# lampu_tidur.net
KiCad netlist of a schematic drawn in EAGLE
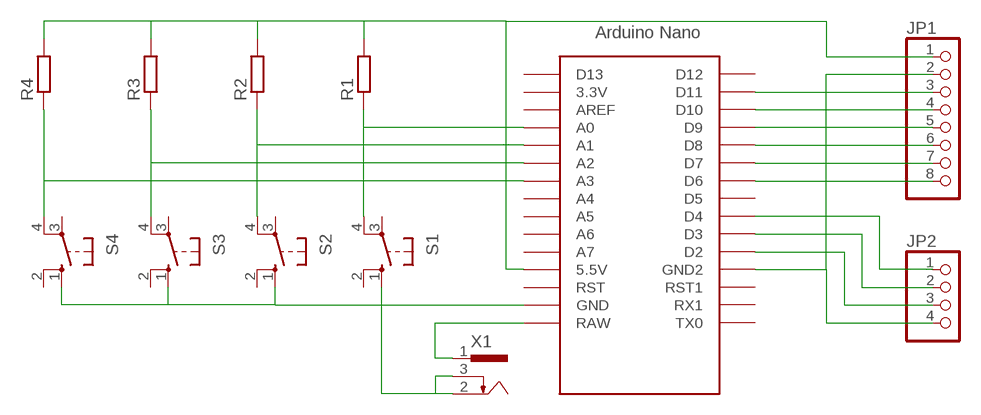
[diagram p0: schematic, sheet 1]

(export (version "E")
  (design (tool "Eeschema 10.0.6"))
  (components
    (comp (ref "JP1")
      (value "PINHD-1X8")
      (footprint "eagle-import:1X08")
      (libsource (lib "eagle-import") (part "PINHD-1X8"))
    )
    (comp (ref "JP2")
      (value "PINHD-1X4")
      (footprint "eagle-import:1X04")
      (libsource (lib "eagle-import") (part "PINHD-1X4"))
    )
    (comp (ref "R1")
      (value "R-EU_0204/7")
      (footprint "eagle-import:0204_7")
      (libsource (lib "eagle-import") (part "R-EU_0204/7"))
    )
    (comp (ref "R2")
      (value "R-EU_0204/7")
      (footprint "eagle-import:0204_7")
      (libsource (lib "eagle-import") (part "R-EU_0204/7"))
    )
    (comp (ref "R3")
      (value "R-EU_0204/7")
      (footprint "eagle-import:0204_7")
      (libsource (lib "eagle-import") (part "R-EU_0204/7"))
    )
    (comp (ref "R4")
      (value "R-EU_0204/7")
      (footprint "eagle-import:0204_7")
      (libsource (lib "eagle-import") (part "R-EU_0204/7"))
    )
    (comp (ref "S1")
      (value "10-XX")
      (footprint "eagle-import:B3F-10XX")
      (fields (field (name "MPN") "B3F-1000"))
      (libsource (lib "eagle-import") (part "10-XX"))
    )
    (comp (ref "S2")
      (value "10-XX")
      (footprint "eagle-import:B3F-10XX")
      (fields (field (name "MPN") "B3F-1000"))
      (libsource (lib "eagle-import") (part "10-XX"))
    )
    (comp (ref "S3")
      (value "10-XX")
      (footprint "eagle-import:B3F-10XX")
      (fields (field (name "MPN") "B3F-1000"))
      (libsource (lib "eagle-import") (part "10-XX"))
    )
    (comp (ref "S4")
      (value "10-XX")
      (footprint "eagle-import:B3F-10XX")
      (fields (field (name "MPN") "B3F-1000"))
      (libsource (lib "eagle-import") (part "10-XX"))
    )
    (comp (ref "U$1")
      (value "NANO")
      (footprint "eagle-import:NANO")
      (libsource (lib "eagle-import") (part "NANO"))
    )
    (comp (ref "X1")
      (value "733980-62")
      (footprint "eagle-import:733980-62")
      (libsource (lib "eagle-import") (part "73398?0-62"))
    )
  )
  (nets
    (net (code "1") (name "Net-(JP1-Pad3)") (class "Default")
      (node (ref "JP1") (pin "3") (pinfunction "3_3") (pintype "passive"))
      (node (ref "U$1") (pin "D11") (pinfunction "D11_D11") (pintype "bidirectional"))
    )
    (net (code "2") (name "Net-(JP1-Pad4)") (class "Default")
      (node (ref "JP1") (pin "4") (pinfunction "4_4") (pintype "passive"))
      (node (ref "U$1") (pin "D10") (pinfunction "D10_D10") (pintype "bidirectional"))
    )
    (net (code "3") (name "Net-(JP1-Pad5)") (class "Default")
      (node (ref "JP1") (pin "5") (pinfunction "5_5") (pintype "passive"))
      (node (ref "U$1") (pin "D9") (pinfunction "D9_D9") (pintype "bidirectional"))
    )
    (net (code "4") (name "Net-(JP1-Pad6)") (class "Default")
      (node (ref "JP1") (pin "6") (pinfunction "6_6") (pintype "passive"))
      (node (ref "U$1") (pin "D8") (pinfunction "D8_D8") (pintype "bidirectional"))
    )
    (net (code "5") (name "Net-(JP1-Pad7)") (class "Default")
      (node (ref "JP1") (pin "7") (pinfunction "7_7") (pintype "passive"))
      (node (ref "U$1") (pin "D7") (pinfunction "D7_D7") (pintype "bidirectional"))
    )
    (net (code "6") (name "Net-(JP1-Pad8)") (class "Default")
      (node (ref "JP1") (pin "8") (pinfunction "8_8") (pintype "passive"))
      (node (ref "U$1") (pin "D6") (pinfunction "D6_D6") (pintype "bidirectional"))
    )
    (net (code "7") (name "Net-(JP2-Pad1)") (class "Default")
      (node (ref "JP2") (pin "1") (pinfunction "1_1") (pintype "passive"))
      (node (ref "U$1") (pin "D4") (pinfunction "D4_D4") (pintype "bidirectional"))
    )
    (net (code "8") (name "Net-(JP2-Pad2)") (class "Default")
      (node (ref "JP2") (pin "2") (pinfunction "2_2") (pintype "passive"))
      (node (ref "U$1") (pin "D3") (pinfunction "D3_D3") (pintype "bidirectional"))
    )
    (net (code "9") (name "Net-(JP2-Pad3)") (class "Default")
      (node (ref "JP2") (pin "3") (pinfunction "3_3") (pintype "passive"))
      (node (ref "U$1") (pin "D2") (pinfunction "D2_D2") (pintype "bidirectional"))
    )
    (net (code "10") (name "Net-(S1-P1)") (class "Default")
      (node (ref "R1") (pin "1") (pinfunction "1_1") (pintype "passive"))
      (node (ref "S1") (pin "4") (pinfunction "P1_4") (pintype "passive"))
      (node (ref "U$1") (pin "A0") (pinfunction "A0_A0") (pintype "bidirectional"))
    )
    (net (code "11") (name "Net-(S1-S)") (class "Default")
      (node (ref "S1") (pin "1") (pinfunction "S_1") (pintype "passive"))
      (node (ref "S2") (pin "1") (pinfunction "S_1") (pintype "passive"))
      (node (ref "S3") (pin "1") (pinfunction "S_1") (pintype "passive"))
      (node (ref "S4") (pin "1") (pinfunction "S_1") (pintype "passive"))
      (node (ref "U$1") (pin "GND") (pinfunction "GND_GND") (pintype "bidirectional"))
      (node (ref "X1") (pin "2") (pinfunction "2_2") (pintype "passive"))
      (node (ref "X1") (pin "3") (pinfunction "3_3") (pintype "passive"))
    )
    (net (code "12") (name "Net-(S2-P1)") (class "Default")
      (node (ref "R2") (pin "1") (pinfunction "1_1") (pintype "passive"))
      (node (ref "S2") (pin "4") (pinfunction "P1_4") (pintype "passive"))
      (node (ref "U$1") (pin "A1") (pinfunction "A1_A1") (pintype "bidirectional"))
    )
    (net (code "13") (name "Net-(S3-P1)") (class "Default")
      (node (ref "R3") (pin "1") (pinfunction "1_1") (pintype "passive"))
      (node (ref "S3") (pin "4") (pinfunction "P1_4") (pintype "passive"))
      (node (ref "U$1") (pin "A2") (pinfunction "A2_A2") (pintype "bidirectional"))
    )
    (net (code "14") (name "Net-(S4-P1)") (class "Default")
      (node (ref "R4") (pin "1") (pinfunction "1_1") (pintype "passive"))
      (node (ref "S4") (pin "4") (pinfunction "P1_4") (pintype "passive"))
      (node (ref "U$1") (pin "A3") (pinfunction "A3_A3") (pintype "bidirectional"))
    )
    (net (code "15") (name "Net-(U$1-5.5V)") (class "Default")
      (node (ref "JP1") (pin "1") (pinfunction "1_1") (pintype "passive"))
      (node (ref "R1") (pin "2") (pinfunction "2_2") (pintype "passive"))
      (node (ref "R2") (pin "2") (pinfunction "2_2") (pintype "passive"))
      (node (ref "R3") (pin "2") (pinfunction "2_2") (pintype "passive"))
      (node (ref "R4") (pin "2") (pinfunction "2_2") (pintype "passive"))
      (node (ref "U$1") (pin "5V") (pinfunction "5.5V_5V") (pintype "bidirectional"))
    )
    (net (code "16") (name "Net-(U$1-GND2)") (class "Default")
      (node (ref "JP1") (pin "2") (pinfunction "2_2") (pintype "passive"))
      (node (ref "JP2") (pin "4") (pinfunction "4_4") (pintype "passive"))
      (node (ref "U$1") (pin "GND1") (pinfunction "GND2_GND1") (pintype "bidirectional"))
    )
    (net (code "17") (name "Net-(U$1-PadRAW)") (class "Default")
      (node (ref "U$1") (pin "RAW") (pinfunction "RAW_RAW") (pintype "bidirectional"))
      (node (ref "X1") (pin "1") (pinfunction "1_1") (pintype "passive"))
    )
    (net (code "18") (name "unconnected-(S1-P-Pad3)") (class "Default")
      (node (ref "S1") (pin "3") (pinfunction "P_3") (pintype "passive"))
    )
    (net (code "19") (name "unconnected-(S1-S1-Pad2)") (class "Default")
      (node (ref "S1") (pin "2") (pinfunction "S1_2") (pintype "passive"))
    )
    (net (code "20") (name "unconnected-(S2-P-Pad3)") (class "Default")
      (node (ref "S2") (pin "3") (pinfunction "P_3") (pintype "passive"))
    )
    (net (code "21") (name "unconnected-(S2-S1-Pad2)") (class "Default")
      (node (ref "S2") (pin "2") (pinfunction "S1_2") (pintype "passive"))
    )
    (net (code "22") (name "unconnected-(S3-P-Pad3)") (class "Default")
      (node (ref "S3") (pin "3") (pinfunction "P_3") (pintype "passive"))
    )
    (net (code "23") (name "unconnected-(S3-S1-Pad2)") (class "Default")
      (node (ref "S3") (pin "2") (pinfunction "S1_2") (pintype "passive"))
    )
    (net (code "24") (name "unconnected-(S4-P-Pad3)") (class "Default")
      (node (ref "S4") (pin "3") (pinfunction "P_3") (pintype "passive"))
    )
    (net (code "25") (name "unconnected-(S4-S1-Pad2)") (class "Default")
      (node (ref "S4") (pin "2") (pinfunction "S1_2") (pintype "passive"))
    )
    (net (code "26") (name "unconnected-(U$1-Pad3.3V)") (class "Default")
      (node (ref "U$1") (pin "3.3V") (pinfunction "3.3V_3.3V") (pintype "bidirectional"))
    )
    (net (code "27") (name "unconnected-(U$1-PadA4)") (class "Default")
      (node (ref "U$1") (pin "A4") (pinfunction "A4_A4") (pintype "bidirectional"))
    )
    (net (code "28") (name "unconnected-(U$1-PadA5)") (class "Default")
      (node (ref "U$1") (pin "A5") (pinfunction "A5_A5") (pintype "bidirectional"))
    )
    (net (code "29") (name "unconnected-(U$1-PadA6)") (class "Default")
      (node (ref "U$1") (pin "A6") (pinfunction "A6_A6") (pintype "bidirectional"))
    )
    (net (code "30") (name "unconnected-(U$1-PadA7)") (class "Default")
      (node (ref "U$1") (pin "A7") (pinfunction "A7_A7") (pintype "bidirectional"))
    )
    (net (code "31") (name "unconnected-(U$1-PadAREF)") (class "Default")
      (node (ref "U$1") (pin "AREF") (pinfunction "AREF_AREF") (pintype "bidirectional"))
    )
    (net (code "32") (name "unconnected-(U$1-PadD5)") (class "Default")
      (node (ref "U$1") (pin "D5") (pinfunction "D5_D5") (pintype "bidirectional"))
    )
    (net (code "33") (name "unconnected-(U$1-PadD12)") (class "Default")
      (node (ref "U$1") (pin "D12") (pinfunction "D12_D12") (pintype "bidirectional"))
    )
    (net (code "34") (name "unconnected-(U$1-PadD13)") (class "Default")
      (node (ref "U$1") (pin "D13") (pinfunction "D13_D13") (pintype "bidirectional"))
    )
    (net (code "35") (name "unconnected-(U$1-PadICSP1)") (class "Default")
      (node (ref "U$1") (pin "ICSP1") (pinfunction "ICSP1_ICSP1") (pintype "bidirectional"))
    )
    (net (code "36") (name "unconnected-(U$1-PadICSP2)") (class "Default")
      (node (ref "U$1") (pin "ICSP2") (pinfunction "ICSP2_ICSP2") (pintype "bidirectional"))
    )
    (net (code "37") (name "unconnected-(U$1-PadICSP3)") (class "Default")
      (node (ref "U$1") (pin "ICSP3") (pinfunction "ICSP3_ICSP3") (pintype "bidirectional"))
    )
    (net (code "38") (name "unconnected-(U$1-PadICSP4)") (class "Default")
      (node (ref "U$1") (pin "ICSP4") (pinfunction "ICSP4_ICSP4") (pintype "bidirectional"))
    )
    (net (code "39") (name "unconnected-(U$1-PadICSP5)") (class "Default")
      (node (ref "U$1") (pin "ICSP5") (pinfunction "ICSP5_ICSP5") (pintype "bidirectional"))
    )
    (net (code "40") (name "unconnected-(U$1-PadICSP6)") (class "Default")
      (node (ref "U$1") (pin "ICSP6") (pinfunction "ICSP6_ICSP6") (pintype "bidirectional"))
    )
    (net (code "41") (name "unconnected-(U$1-PadRST)") (class "Default")
      (node (ref "U$1") (pin "RST") (pinfunction "RST_RST") (pintype "bidirectional"))
    )
    (net (code "42") (name "unconnected-(U$1-PadRST1)") (class "Default")
      (node (ref "U$1") (pin "RST1") (pinfunction "RST1_RST1") (pintype "bidirectional"))
    )
    (net (code "43") (name "unconnected-(U$1-PadRX1)") (class "Default")
      (node (ref "U$1") (pin "RX1") (pinfunction "RX1_RX1") (pintype "bidirectional"))
    )
    (net (code "44") (name "unconnected-(U$1-PadTX0)") (class "Default")
      (node (ref "U$1") (pin "TX0") (pinfunction "TX0_TX0") (pintype "bidirectional"))
    )
  )
)
